# Glucometer-E_C_-_Full_V1.net
KiCad netlist of a schematic drawn in Altium Designer
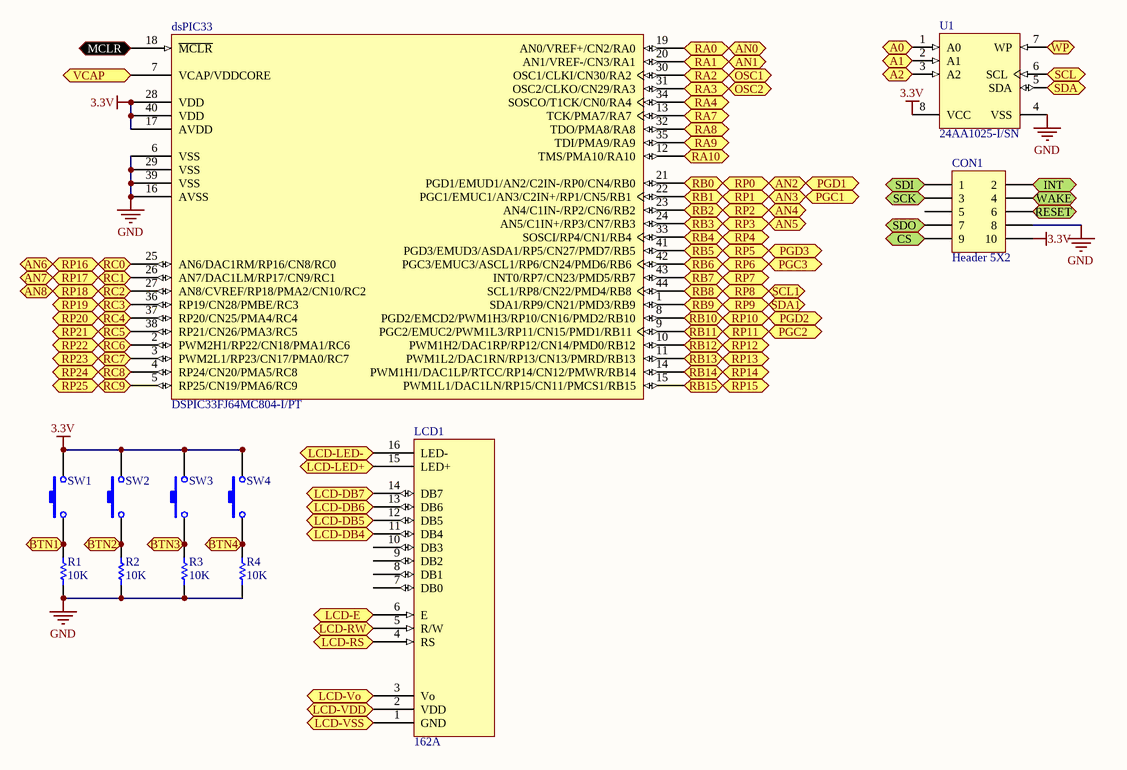
[diagram p0: Glucometer-E.C.- Full V1.SchDoc]

(export (version "E")
  (design (tool "Eeschema 10.0.6"))
  (components
    (comp (ref "CON1")
      (value "Header 5X2")
      (footprint "HDR2X5")
      (description "Header, 5-Pin, Dual row")
      (fields (field (name "PUBLISHER") "Altium Limited"))
      (libsource (lib "Miscellaneous Connectors") (part "Header 5X2"))
    )
    (comp (ref "dsPIC33")
      (value "DSPIC33FJ64MC804-I/PT")
      (footprint "TQFP-PT44_N")
      (fields (field (name "PUBLISHER") "Altium Limited"))
      (libsource (lib "Microchip DSC 16-Bit dsPIC33F") (part "DSPIC33FJ64MC804-I/PT"))
    )
    (comp (ref "LCD1")
      (value "162A")
      (footprint "Spirit_Level_Project:162A")
      (description "16 char * 2 line LCD character display with b/light")
      (libsource (lib "SpiritLevel_2E") (part "162A"))
    )
    (comp (ref "R1")
      (value "10K")
      (footprint "AXIAL-0.3")
      (description "Resistor")
      (fields (field (name "Comment") "Res1") (field (name "PUBLISHER") "Altium Limited"))
      (libsource (lib "Miscellaneous Devices") (part "Res1"))
    )
    (comp (ref "R2")
      (value "10K")
      (footprint "AXIAL-0.3")
      (description "Resistor")
      (fields (field (name "Comment") "Res1") (field (name "PUBLISHER") "Altium Limited"))
      (libsource (lib "Miscellaneous Devices") (part "Res1"))
    )
    (comp (ref "R3")
      (value "10K")
      (footprint "AXIAL-0.3")
      (description "Resistor")
      (fields (field (name "Comment") "Res1") (field (name "PUBLISHER") "Altium Limited"))
      (libsource (lib "Miscellaneous Devices") (part "Res1"))
    )
    (comp (ref "R4")
      (value "10K")
      (footprint "AXIAL-0.3")
      (description "Resistor")
      (fields (field (name "Comment") "Res1") (field (name "PUBLISHER") "Altium Limited"))
      (libsource (lib "Miscellaneous Devices") (part "Res1"))
    )
    (comp (ref "SW1")
      (value "SW-PB")
      (footprint "SPST-2")
      (description "Switch")
      (fields (field (name "PUBLISHER") "Altium Limited"))
      (libsource (lib "Miscellaneous Devices") (part "SW-PB"))
    )
    (comp (ref "SW2")
      (value "SW-PB")
      (footprint "SPST-2")
      (description "Switch")
      (fields (field (name "PUBLISHER") "Altium Limited"))
      (libsource (lib "Miscellaneous Devices") (part "SW-PB"))
    )
    (comp (ref "SW3")
      (value "SW-PB")
      (footprint "SPST-2")
      (description "Switch")
      (fields (field (name "PUBLISHER") "Altium Limited"))
      (libsource (lib "Miscellaneous Devices") (part "SW-PB"))
    )
    (comp (ref "SW4")
      (value "SW-PB")
      (footprint "SPST-2")
      (description "Switch")
      (fields (field (name "PUBLISHER") "Altium Limited"))
      (libsource (lib "Miscellaneous Devices") (part "SW-PB"))
    )
    (comp (ref "U1")
      (value "24AA1025-I/SN")
      (footprint "SOIC-SN8_N")
      (description "1 Mbit, 400kHz, 1.7V, 8-Pin SOIC 150mil, Industrial Temperature")
      (fields (field (name "PUBLISHER") "Altium Limited"))
      (libsource (lib "Microchip Memory I2C Serial EEPROM") (part "24AA1025-I/SN"))
    )
  )
  (nets
    (net (code "1") (name "/A0") (class "Default")
      (node (ref "U1") (pin "1") (pinfunction "A0_1") (pintype "input"))
    )
    (net (code "2") (name "/A1") (class "Default")
      (node (ref "U1") (pin "2") (pinfunction "A1_2") (pintype "input"))
    )
    (net (code "3") (name "/A2") (class "Default")
      (node (ref "U1") (pin "3") (pinfunction "A2_3") (pintype "input"))
    )
    (net (code "13") (name "/BTN1") (class "Default")
      (node (ref "R1") (pin "2") (pinfunction "2_2") (pintype "passive"))
      (node (ref "SW1") (pin "1") (pinfunction "1_1") (pintype "passive"))
    )
    (net (code "14") (name "/BTN2") (class "Default")
      (node (ref "R2") (pin "2") (pinfunction "2_2") (pintype "passive"))
      (node (ref "SW2") (pin "1") (pinfunction "1_1") (pintype "passive"))
    )
    (net (code "15") (name "/BTN3") (class "Default")
      (node (ref "R3") (pin "2") (pinfunction "2_2") (pintype "passive"))
      (node (ref "SW3") (pin "1") (pinfunction "1_1") (pintype "passive"))
    )
    (net (code "16") (name "/BTN4") (class "Default")
      (node (ref "R4") (pin "2") (pinfunction "2_2") (pintype "passive"))
      (node (ref "SW4") (pin "1") (pinfunction "1_1") (pintype "passive"))
    )
    (net (code "17") (name "/CS") (class "Default")
      (node (ref "CON1") (pin "9") (pinfunction "9_9") (pintype "passive"))
    )
    (net (code "18") (name "/INT") (class "Default")
      (node (ref "CON1") (pin "2") (pinfunction "2_2") (pintype "passive"))
    )
    (net (code "19") (name "/LCD-DB4") (class "Default")
      (node (ref "LCD1") (pin "11") (pinfunction "DB4_11") (pintype "bidirectional"))
    )
    (net (code "20") (name "/LCD-DB5") (class "Default")
      (node (ref "LCD1") (pin "12") (pinfunction "DB5_12") (pintype "bidirectional"))
    )
    (net (code "21") (name "/LCD-DB6") (class "Default")
      (node (ref "LCD1") (pin "13") (pinfunction "DB6_13") (pintype "bidirectional"))
    )
    (net (code "22") (name "/LCD-DB7") (class "Default")
      (node (ref "LCD1") (pin "14") (pinfunction "DB7_14") (pintype "bidirectional"))
    )
    (net (code "23") (name "/LCD-E") (class "Default")
      (node (ref "LCD1") (pin "6") (pinfunction "E_6") (pintype "input"))
    )
    (net (code "24") (name "/LCD-LED+") (class "Default")
      (node (ref "LCD1") (pin "15") (pinfunction "LED+_15") (pintype "power_in"))
    )
    (net (code "25") (name "/LCD-LED-") (class "Default")
      (node (ref "LCD1") (pin "16") (pinfunction "LED-_16") (pintype "power_in"))
    )
    (net (code "26") (name "/LCD-RS") (class "Default")
      (node (ref "LCD1") (pin "4") (pinfunction "RS_4") (pintype "input"))
    )
    (net (code "27") (name "/LCD-RW") (class "Default")
      (node (ref "LCD1") (pin "5") (pinfunction "R/W_5") (pintype "input"))
    )
    (net (code "28") (name "/LCD-VDD") (class "Default")
      (node (ref "LCD1") (pin "2") (pinfunction "VDD_2") (pintype "power_in"))
    )
    (net (code "29") (name "/LCD-VSS") (class "Default")
      (node (ref "LCD1") (pin "1") (pinfunction "GND_1") (pintype "power_in"))
    )
    (net (code "30") (name "/LCD-Vo") (class "Default")
      (node (ref "LCD1") (pin "3") (pinfunction "Vo_3") (pintype "tri_state"))
    )
    (net (code "31") (name "/MCLR") (class "Default")
      (node (ref "dsPIC33") (pin "18") (pinfunction "~{MCLR}_18") (pintype "input"))
    )
    (net (code "40") (name "/RA0") (class "Default")
      (node (ref "dsPIC33") (pin "19") (pinfunction "AN0/VREF+/CN2/RA0_19") (pintype "bidirectional"))
    )
    (net (code "41") (name "/RA1") (class "Default")
      (node (ref "dsPIC33") (pin "20") (pinfunction "AN1/VREF-/CN3/RA1_20") (pintype "bidirectional"))
    )
    (net (code "42") (name "/RA2") (class "Default")
      (node (ref "dsPIC33") (pin "30") (pinfunction "OSC1/CLKI/CN30/RA2_30") (pintype "bidirectional"))
    )
    (net (code "43") (name "/RA3") (class "Default")
      (node (ref "dsPIC33") (pin "31") (pinfunction "OSC2/CLKO/CN29/RA3_31") (pintype "bidirectional"))
    )
    (net (code "44") (name "/RA4") (class "Default")
      (node (ref "dsPIC33") (pin "34") (pinfunction "SOSCO/T1CK/CN0/RA4_34") (pintype "bidirectional"))
    )
    (net (code "45") (name "/RA7") (class "Default")
      (node (ref "dsPIC33") (pin "13") (pinfunction "TCK/PMA7/RA7_13") (pintype "bidirectional"))
    )
    (net (code "46") (name "/RA8") (class "Default")
      (node (ref "dsPIC33") (pin "32") (pinfunction "TDO/PMA8/RA8_32") (pintype "bidirectional"))
    )
    (net (code "47") (name "/RA9") (class "Default")
      (node (ref "dsPIC33") (pin "35") (pinfunction "TDI/PMA9/RA9_35") (pintype "bidirectional"))
    )
    (net (code "48") (name "/RA10") (class "Default")
      (node (ref "dsPIC33") (pin "12") (pinfunction "TMS/PMA10/RA10_12") (pintype "bidirectional"))
    )
    (net (code "49") (name "/RB0") (class "Default")
      (node (ref "dsPIC33") (pin "21") (pinfunction "PGD1/EMUD1/AN2/C2IN-/RP0/CN4/RB0_21") (pintype "bidirectional"))
    )
    (net (code "50") (name "/RB1") (class "Default")
      (node (ref "dsPIC33") (pin "22") (pinfunction "PGC1/EMUC1/AN3/C2IN+/RP1/CN5/RB1_22") (pintype "bidirectional"))
    )
    (net (code "51") (name "/RB2") (class "Default")
      (node (ref "dsPIC33") (pin "23") (pinfunction "AN4/C1IN-/RP2/CN6/RB2_23") (pintype "bidirectional"))
    )
    (net (code "52") (name "/RB3") (class "Default")
      (node (ref "dsPIC33") (pin "24") (pinfunction "AN5/C1IN+/RP3/CN7/RB3_24") (pintype "bidirectional"))
    )
    (net (code "53") (name "/RB4") (class "Default")
      (node (ref "dsPIC33") (pin "33") (pinfunction "SOSCI/RP4/CN1/RB4_33") (pintype "bidirectional"))
    )
    (net (code "54") (name "/RB5") (class "Default")
      (node (ref "dsPIC33") (pin "41") (pinfunction "PGD3/EMUD3/ASDA1/RP5/CN27/PMD7/RB5_41") (pintype "bidirectional"))
    )
    (net (code "55") (name "/RB6") (class "Default")
      (node (ref "dsPIC33") (pin "42") (pinfunction "PGC3/EMUC3/ASCL1/RP6/CN24/PMD6/RB6_42") (pintype "bidirectional"))
    )
    (net (code "56") (name "/RB7") (class "Default")
      (node (ref "dsPIC33") (pin "43") (pinfunction "INT0/RP7/CN23/PMD5/RB7_43") (pintype "bidirectional"))
    )
    (net (code "57") (name "/RB8") (class "Default")
      (node (ref "dsPIC33") (pin "44") (pinfunction "SCL1/RP8/CN22/PMD4/RB8_44") (pintype "bidirectional"))
    )
    (net (code "58") (name "/RB9") (class "Default")
      (node (ref "dsPIC33") (pin "1") (pinfunction "SDA1/RP9/CN21/PMD3/RB9_1") (pintype "bidirectional"))
    )
    (net (code "59") (name "/RB10") (class "Default")
      (node (ref "dsPIC33") (pin "8") (pinfunction "PGD2/EMCD2/PWM1H3/RP10/CN16/PMD2/RB10_8") (pintype "bidirectional"))
    )
    (net (code "60") (name "/RB11") (class "Default")
      (node (ref "dsPIC33") (pin "9") (pinfunction "PGC2/EMUC2/PWM1L3/RP11/CN15/PMD1/RB11_9") (pintype "bidirectional"))
    )
    (net (code "61") (name "/RB12") (class "Default")
      (node (ref "dsPIC33") (pin "10") (pinfunction "PWM1H2/DAC1RP/RP12/CN14/PMD0/RB12_10") (pintype "bidirectional"))
    )
    (net (code "62") (name "/RB13") (class "Default")
      (node (ref "dsPIC33") (pin "11") (pinfunction "PWM1L2/DAC1RN/RP13/CN13/PMRD/RB13_11") (pintype "bidirectional"))
    )
    (net (code "63") (name "/RB14") (class "Default")
      (node (ref "dsPIC33") (pin "14") (pinfunction "PWM1H1/DAC1LP/RTCC/RP14/CN12/PMWR/RB14_14") (pintype "bidirectional"))
    )
    (net (code "64") (name "/RB15") (class "Default")
      (node (ref "dsPIC33") (pin "15") (pinfunction "PWM1L1/DAC1LN/RP15/CN11/PMCS1/RB15_15") (pintype "bidirectional"))
    )
    (net (code "65") (name "/RC0") (class "Default")
      (node (ref "dsPIC33") (pin "25") (pinfunction "AN6/DAC1RM/RP16/CN8/RC0_25") (pintype "bidirectional"))
    )
    (net (code "66") (name "/RC1") (class "Default")
      (node (ref "dsPIC33") (pin "26") (pinfunction "AN7/DAC1LM/RP17/CN9/RC1_26") (pintype "bidirectional"))
    )
    (net (code "67") (name "/RC2") (class "Default")
      (node (ref "dsPIC33") (pin "27") (pinfunction "AN8/CVREF/RP18/PMA2/CN10/RC2_27") (pintype "bidirectional"))
    )
    (net (code "68") (name "/RC3") (class "Default")
      (node (ref "dsPIC33") (pin "36") (pinfunction "RP19/CN28/PMBE/RC3_36") (pintype "bidirectional"))
    )
    (net (code "69") (name "/RC4") (class "Default")
      (node (ref "dsPIC33") (pin "37") (pinfunction "RP20/CN25/PMA4/RC4_37") (pintype "bidirectional"))
    )
    (net (code "70") (name "/RC5") (class "Default")
      (node (ref "dsPIC33") (pin "38") (pinfunction "RP21/CN26/PMA3/RC5_38") (pintype "bidirectional"))
    )
    (net (code "71") (name "/RC6") (class "Default")
      (node (ref "dsPIC33") (pin "2") (pinfunction "PWM2H1/RP22/CN18/PMA1/RC6_2") (pintype "bidirectional"))
    )
    (net (code "72") (name "/RC7") (class "Default")
      (node (ref "dsPIC33") (pin "3") (pinfunction "PWM2L1/RP23/CN17/PMA0/RC7_3") (pintype "bidirectional"))
    )
    (net (code "73") (name "/RC8") (class "Default")
      (node (ref "dsPIC33") (pin "4") (pinfunction "RP24/CN20/PMA5/RC8_4") (pintype "bidirectional"))
    )
    (net (code "74") (name "/RC9") (class "Default")
      (node (ref "dsPIC33") (pin "5") (pinfunction "RP25/CN19/PMA6/RC9_5") (pintype "bidirectional"))
    )
    (net (code "75") (name "/RESET") (class "Default")
      (node (ref "CON1") (pin "6") (pinfunction "6_6") (pintype "passive"))
    )
    (net (code "92") (name "/SCK") (class "Default")
      (node (ref "CON1") (pin "3") (pinfunction "3_3") (pintype "passive"))
    )
    (net (code "93") (name "/SCL") (class "Default")
      (node (ref "U1") (pin "6") (pinfunction "SCL_6") (pintype "input"))
    )
    (net (code "95") (name "/SDA") (class "Default")
      (node (ref "U1") (pin "5") (pinfunction "SDA_5") (pintype "bidirectional"))
    )
    (net (code "97") (name "/SDI") (class "Default")
      (node (ref "CON1") (pin "1") (pinfunction "1_1") (pintype "passive"))
    )
    (net (code "98") (name "/SDO") (class "Default")
      (node (ref "CON1") (pin "7") (pinfunction "7_7") (pintype "passive"))
    )
    (net (code "99") (name "/VCAP") (class "Default")
      (node (ref "dsPIC33") (pin "7") (pinfunction "VCAP/VDDCORE_7") (pintype "power_in"))
    )
    (net (code "100") (name "/WAKE") (class "Default")
      (node (ref "CON1") (pin "4") (pinfunction "4_4") (pintype "passive"))
    )
    (net (code "101") (name "/WP") (class "Default")
      (node (ref "U1") (pin "7") (pinfunction "WP_7") (pintype "input"))
    )
    (net (code "102") (name "3.3V") (class "Default")
      (node (ref "CON1") (pin "10") (pinfunction "10_10") (pintype "passive"))
      (node (ref "SW1") (pin "2") (pinfunction "2_2") (pintype "passive"))
      (node (ref "SW2") (pin "2") (pinfunction "2_2") (pintype "passive"))
      (node (ref "SW3") (pin "2") (pinfunction "2_2") (pintype "passive"))
      (node (ref "SW4") (pin "2") (pinfunction "2_2") (pintype "passive"))
      (node (ref "U1") (pin "8") (pinfunction "VCC_8") (pintype "power_in"))
      (node (ref "dsPIC33") (pin "17") (pinfunction "AVDD_17") (pintype "power_in"))
      (node (ref "dsPIC33") (pin "28") (pinfunction "VDD_28") (pintype "power_in"))
      (node (ref "dsPIC33") (pin "40") (pinfunction "VDD_40") (pintype "power_in"))
    )
    (net (code "103") (name "GND") (class "Default")
      (node (ref "CON1") (pin "8") (pinfunction "8_8") (pintype "passive"))
      (node (ref "R1") (pin "1") (pinfunction "1_1") (pintype "passive"))
      (node (ref "R2") (pin "1") (pinfunction "1_1") (pintype "passive"))
      (node (ref "R3") (pin "1") (pinfunction "1_1") (pintype "passive"))
      (node (ref "R4") (pin "1") (pinfunction "1_1") (pintype "passive"))
      (node (ref "U1") (pin "4") (pinfunction "VSS_4") (pintype "power_in"))
      (node (ref "dsPIC33") (pin "16") (pinfunction "AVSS_16") (pintype "power_in"))
      (node (ref "dsPIC33") (pin "29") (pinfunction "VSS_29") (pintype "power_in"))
      (node (ref "dsPIC33") (pin "39") (pinfunction "VSS_39") (pintype "power_in"))
      (node (ref "dsPIC33") (pin "6") (pinfunction "VSS_6") (pintype "power_in"))
    )
    (net (code "104") (name "unconnected-(CON1-Pad5)") (class "Default")
      (node (ref "CON1") (pin "5") (pinfunction "5_5") (pintype "passive"))
    )
    (net (code "105") (name "unconnected-(LCD1-DB0-Pad7)") (class "Default")
      (node (ref "LCD1") (pin "7") (pinfunction "DB0_7") (pintype "bidirectional"))
    )
    (net (code "106") (name "unconnected-(LCD1-DB1-Pad8)") (class "Default")
      (node (ref "LCD1") (pin "8") (pinfunction "DB1_8") (pintype "bidirectional"))
    )
    (net (code "107") (name "unconnected-(LCD1-DB2-Pad9)") (class "Default")
      (node (ref "LCD1") (pin "9") (pinfunction "DB2_9") (pintype "bidirectional"))
    )
    (net (code "108") (name "unconnected-(LCD1-DB3-Pad10)") (class "Default")
      (node (ref "LCD1") (pin "10") (pinfunction "DB3_10") (pintype "bidirectional"))
    )
  )
)
